# power_supply.net
KiCad netlist of a schematic drawn in Altium Designer
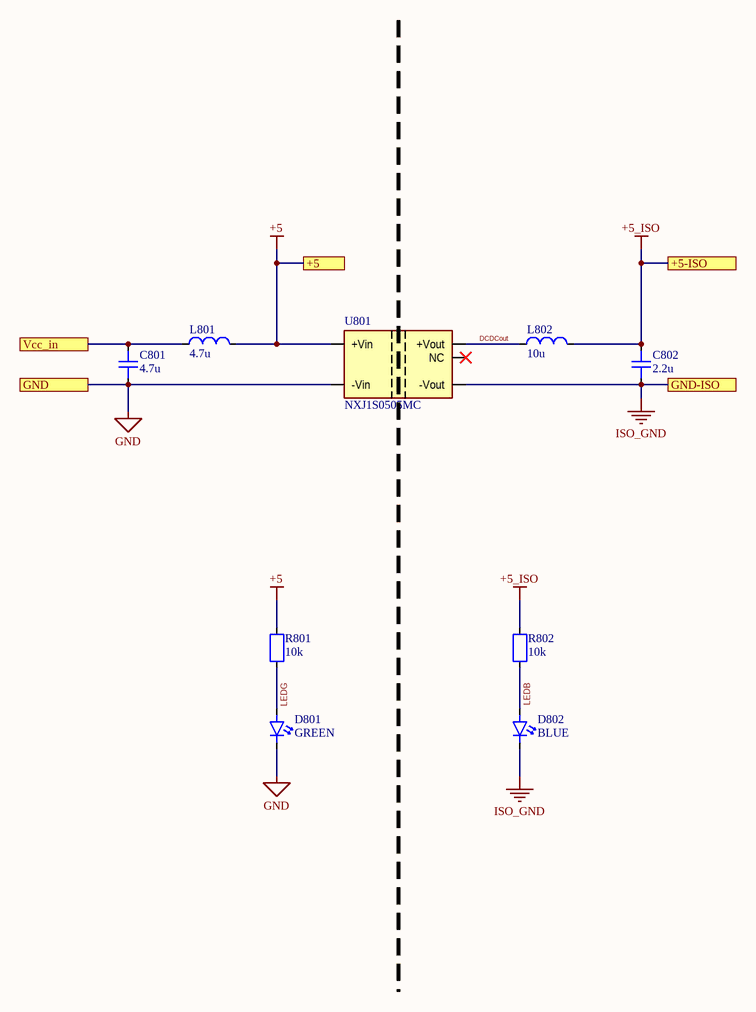
[diagram p0: power_supply.SchDoc]

(export (version "E")
  (design (tool "Eeschema 10.0.6"))
  (components
    (comp (ref "C801")
      (value "4.7u")
      (footprint "CAP0603")
      (libsource (lib "schematic_library") (part "Capacitor"))
    )
    (comp (ref "C802")
      (value "2.2u")
      (footprint "CAP0603")
      (libsource (lib "schematic_library") (part "Capacitor"))
    )
    (comp (ref "D801")
      (value "GREEN")
      (footprint "LED0603")
      (libsource (lib "schematic_library") (part "LED"))
    )
    (comp (ref "D802")
      (value "BLUE")
      (footprint "LED0603")
      (libsource (lib "schematic_library") (part "LED"))
    )
    (comp (ref "L801")
      (value "4.7u")
      (footprint "FP-8200-MFG")
      (libsource (lib "schematic_library") (part "Inductor"))
    )
    (comp (ref "L802")
      (value "10u")
      (footprint "FP-8200-MFG")
      (libsource (lib "schematic_library") (part "Inductor"))
    )
    (comp (ref "R801")
      (value "10k")
      (footprint "RES0603")
      (libsource (lib "schematic_library") (part "Resistor"))
    )
    (comp (ref "R802")
      (value "10k")
      (footprint "RES0603")
      (libsource (lib "schematic_library") (part "Resistor"))
    )
    (comp (ref "U801")
      (value "NXJ1S0505MC")
      (footprint "NXJ1")
      (description "Isolated DC/DC Converters - SMD SM 1W 5V-5V SINGLE 4.2KV")
      (libsource (lib "schematic_library") (part "NXJ1S0505MC"))
    )
  )
  (nets
    (net (code "1") (name "+5") (class "Default")
      (node (ref "L801") (pin "2") (pintype "passive"))
      (node (ref "R801") (pin "1") (pintype "passive"))
      (node (ref "U801") (pin "3") (pinfunction "+Vin_3") (pintype "passive"))
    )
    (net (code "2") (name "+5_ISO") (class "Default")
      (node (ref "C802") (pin "1") (pintype "passive"))
      (node (ref "L802") (pin "2") (pintype "passive"))
      (node (ref "R802") (pin "1") (pintype "passive"))
    )
    (net (code "3") (name "/DCDCout") (class "Default")
      (node (ref "L802") (pin "1") (pintype "passive"))
      (node (ref "U801") (pin "8") (pinfunction "+Vout_8") (pintype "passive"))
    )
    (net (code "4") (name "/LEDB") (class "Default")
      (node (ref "D802") (pin "1") (pintype "passive"))
      (node (ref "R802") (pin "2") (pintype "passive"))
    )
    (net (code "5") (name "/LEDG") (class "Default")
      (node (ref "D801") (pin "1") (pintype "passive"))
      (node (ref "R801") (pin "2") (pintype "passive"))
    )
    (net (code "6") (name "/Vcc_in") (class "Default")
      (node (ref "C801") (pin "1") (pintype "passive"))
      (node (ref "L801") (pin "1") (pintype "passive"))
    )
    (net (code "7") (name "GND") (class "Default")
      (node (ref "C801") (pin "2") (pintype "passive"))
      (node (ref "D801") (pin "2") (pintype "passive"))
      (node (ref "U801") (pin "1") (pinfunction "-Vin_1") (pintype "passive"))
    )
    (net (code "8") (name "ISO_GND") (class "Default")
      (node (ref "C802") (pin "2") (pintype "passive"))
      (node (ref "D802") (pin "2") (pintype "passive"))
      (node (ref "U801") (pin "7") (pinfunction "-Vout_7") (pintype "passive"))
    )
    (net (code "9") (name "unconnected-(U801-NC-Pad14)") (class "Default")
      (node (ref "U801") (pin "14") (pinfunction "NC_14") (pintype "passive+no_connect"))
    )
  )
)
